# Option_DDR3_96ball.net
KiCad netlist of a schematic drawn in Altium Designer
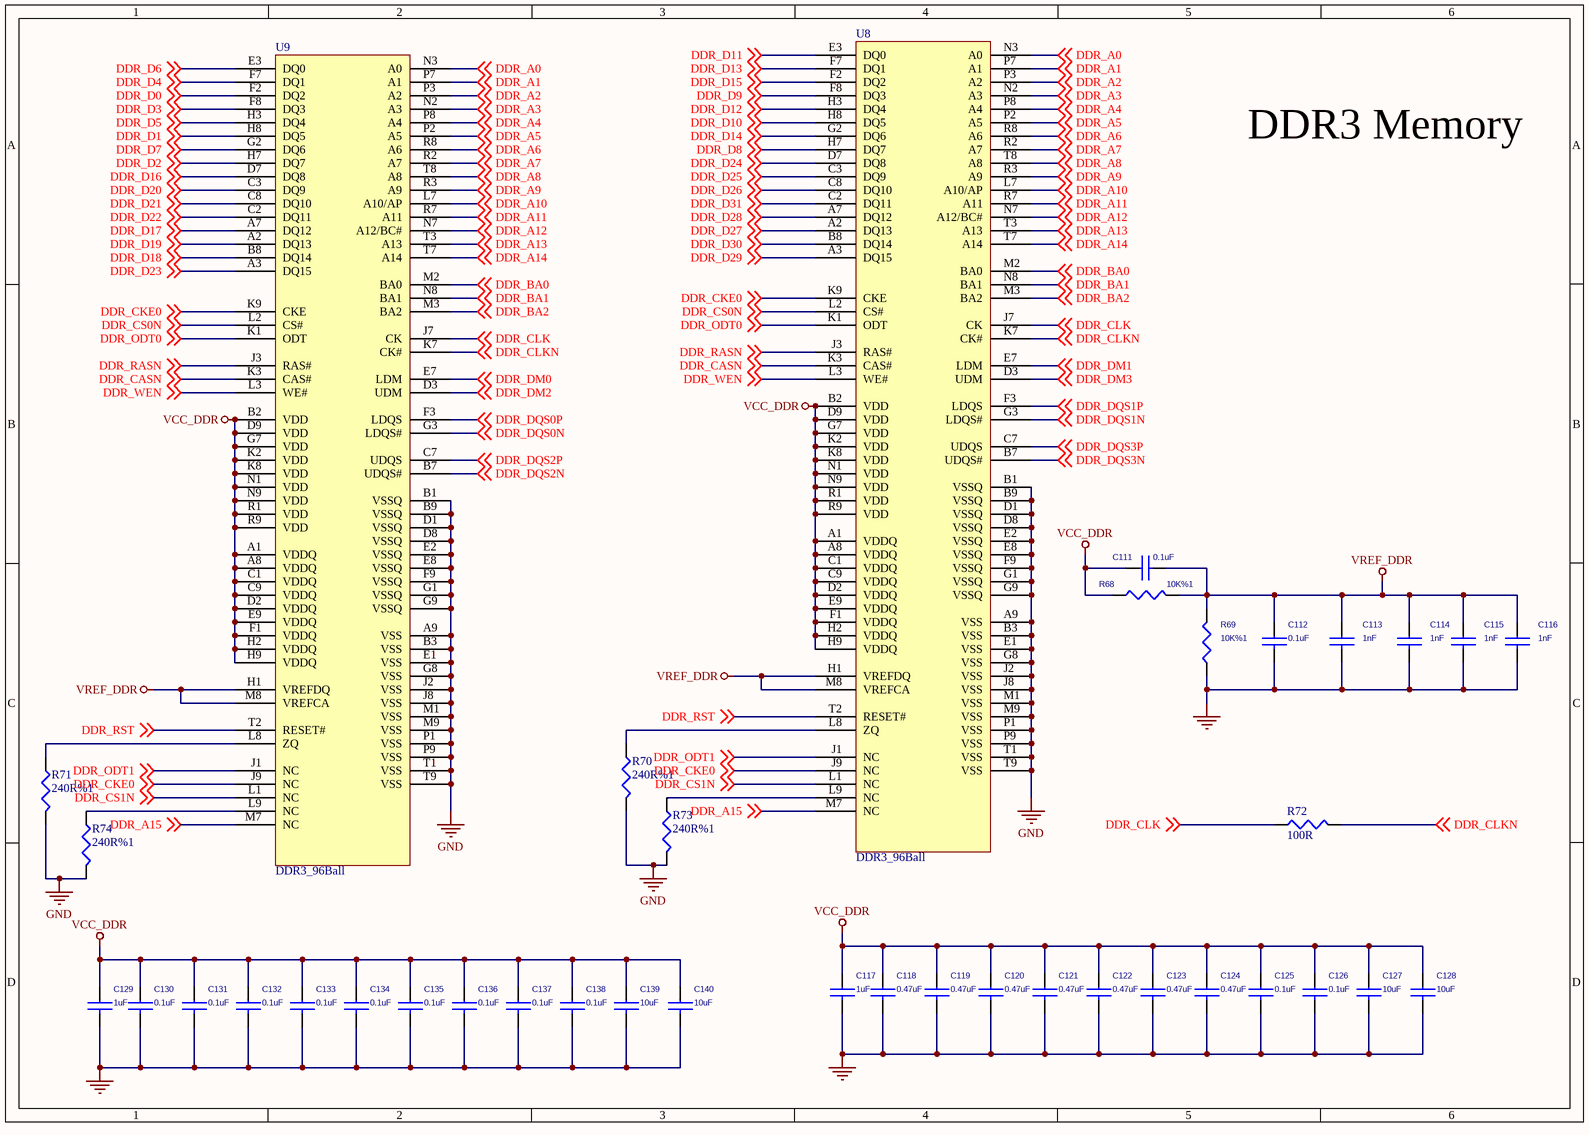
[diagram p0: Option_DDR3_96ball.SchDoc]

(export (version "E")
  (design (tool "Eeschema 10.0.6"))
  (components
    (comp (ref "C111") (value "0.1uF") (footprint "C0402") (libsource (lib "*") (part "CAP NP_0")))
    (comp (ref "C112") (value "0.1uF") (footprint "C0402") (libsource (lib "*") (part "CAP NP_0")))
    (comp (ref "C113") (value "1nF") (footprint "C0402") (libsource (lib "*") (part "CAP NP_0")))
    (comp (ref "C114") (value "1nF") (footprint "C0402") (libsource (lib "*") (part "CAP NP_0")))
    (comp (ref "C115") (value "1nF") (footprint "C0402") (libsource (lib "*") (part "CAP NP_0")))
    (comp (ref "C116") (value "1nF") (footprint "C0402") (libsource (lib "*") (part "CAP NP_0")))
    (comp (ref "C117")
      (value "1uF")
      (footprint "C0402")
      (description "RoHS CHIP CAP 1uF +10/-10% X5R")
      (libsource (lib "*") (part "CAP NP"))
    )
    (comp (ref "C118")
      (value "0.47uF")
      (footprint "C0402")
      (description "RoHS CHIP CAP 1uF +10/-10% X5R")
      (libsource (lib "*") (part "CAP NP"))
    )
    (comp (ref "C119")
      (value "0.47uF")
      (footprint "C0402")
      (description "RoHS CHIP CAP 1uF +10/-10% X5R")
      (libsource (lib "*") (part "CAP NP"))
    )
    (comp (ref "C120")
      (value "0.47uF")
      (footprint "C0402")
      (description "RoHS CHIP CAP 1uF +10/-10% X5R")
      (libsource (lib "*") (part "CAP NP"))
    )
    (comp (ref "C121")
      (value "0.47uF")
      (footprint "C0402")
      (description "RoHS CHIP CAP 1uF +10/-10% X5R")
      (libsource (lib "*") (part "CAP NP"))
    )
    (comp (ref "C122")
      (value "0.47uF")
      (footprint "C0402")
      (description "RoHS CHIP CAP 1uF +10/-10% X5R")
      (libsource (lib "*") (part "CAP NP"))
    )
    (comp (ref "C123")
      (value "0.47uF")
      (footprint "C0402")
      (description "RoHS CHIP CAP 1uF +10/-10% X5R")
      (libsource (lib "*") (part "CAP NP"))
    )
    (comp (ref "C124")
      (value "0.47uF")
      (footprint "C0402")
      (description "RoHS CHIP CAP 1uF +10/-10% X5R")
      (libsource (lib "*") (part "CAP NP"))
    )
    (comp (ref "C125")
      (value "0.1uF")
      (footprint "C0402")
      (description "RoHS CHIP CAP 0.1uF +10/-10% X7R")
      (libsource (lib "*") (part "CAP NP"))
    )
    (comp (ref "C126")
      (value "0.1uF")
      (footprint "C0402")
      (description "RoHS CHIP CAP 0.1uF +10/-10% X7R")
      (libsource (lib "*") (part "CAP NP"))
    )
    (comp (ref "C127")
      (value "10uF")
      (footprint "C0805")
      (description "RoHS CHIP CAP 0.1uF +10/-10% X7R")
      (libsource (lib "*") (part "CAP NP"))
    )
    (comp (ref "C128")
      (value "10uF")
      (footprint "C0805")
      (description "RoHS CHIP CAP 0.1uF +10/-10% X7R")
      (libsource (lib "*") (part "CAP NP"))
    )
    (comp (ref "C129")
      (value "1uF")
      (footprint "C0402")
      (description "RoHS CHIP CAP 1uF +10/-10% X5R")
      (libsource (lib "*") (part "CAP NP"))
    )
    (comp (ref "C130")
      (value "0.1uF")
      (footprint "C0402")
      (description "RoHS CHIP CAP 1uF +10/-10% X5R")
      (libsource (lib "*") (part "CAP NP"))
    )
    (comp (ref "C131")
      (value "0.1uF")
      (footprint "C0402")
      (description "RoHS CHIP CAP 0.1uF +10/-10% X7R")
      (libsource (lib "*") (part "CAP NP"))
    )
    (comp (ref "C132")
      (value "0.1uF")
      (footprint "C0402")
      (description "RoHS CHIP CAP 0.1uF +10/-10% X7R")
      (libsource (lib "*") (part "CAP NP"))
    )
    (comp (ref "C133")
      (value "0.1uF")
      (footprint "C0402")
      (description "RoHS CHIP CAP 0.1uF +10/-10% X7R")
      (libsource (lib "*") (part "CAP NP"))
    )
    (comp (ref "C134")
      (value "0.1uF")
      (footprint "C0402")
      (description "RoHS CHIP CAP 0.1uF +10/-10% X7R")
      (libsource (lib "*") (part "CAP NP"))
    )
    (comp (ref "C135")
      (value "0.1uF")
      (footprint "C0402")
      (description "RoHS CHIP CAP 0.1uF +10/-10% X7R")
      (libsource (lib "*") (part "CAP NP"))
    )
    (comp (ref "C136")
      (value "0.1uF")
      (footprint "C0402")
      (description "RoHS CHIP CAP 0.1uF +10/-10% X7R")
      (libsource (lib "*") (part "CAP NP"))
    )
    (comp (ref "C137")
      (value "0.1uF")
      (footprint "C0402")
      (description "RoHS CHIP CAP 0.1uF +10/-10% X7R")
      (libsource (lib "*") (part "CAP NP"))
    )
    (comp (ref "C138")
      (value "0.1uF")
      (footprint "C0402")
      (description "RoHS CHIP CAP 0.1uF +10/-10% X7R")
      (libsource (lib "*") (part "CAP NP"))
    )
    (comp (ref "C139")
      (value "10uF")
      (footprint "C0805")
      (description "RoHS CHIP CAP 0.1uF +10/-10% X7R")
      (libsource (lib "*") (part "CAP NP"))
    )
    (comp (ref "C140")
      (value "10uF")
      (footprint "C0805")
      (description "RoHS CHIP CAP 0.1uF +10/-10% X7R")
      (libsource (lib "*") (part "CAP NP"))
    )
    (comp (ref "R68")
      (value "10K%1")
      (footprint "R0402")
      (description "贴片电阻")
      (libsource (lib "*") (part "RESISTOR_0"))
    )
    (comp (ref "R69")
      (value "10K%1")
      (footprint "R0402")
      (description "贴片电阻")
      (libsource (lib "*") (part "RESISTOR_0"))
    )
    (comp (ref "R70")
      (value "240R%1")
      (footprint "R0402")
      (libsource (lib "RK3128_BETA_V03_20151231_Library") (part "RESISTOR"))
    )
    (comp (ref "R71")
      (value "240R%1")
      (footprint "R0402")
      (libsource (lib "RK3128_BETA_V03_20151231_Library") (part "RESISTOR"))
    )
    (comp (ref "R72")
      (value "100R")
      (footprint "R0402")
      (libsource (lib "RK3128_BETA_V03_20151231_Library") (part "RESISTOR"))
    )
    (comp (ref "R73")
      (value "240R%1")
      (footprint "R0402")
      (libsource (lib "RK3128_BETA_V03_20151231_Library") (part "RESISTOR"))
    )
    (comp (ref "R74")
      (value "240R%1")
      (footprint "R0402")
      (libsource (lib "RK3128_BETA_V03_20151231_Library") (part "RESISTOR"))
    )
    (comp (ref "U8") (value "DDR3_96Ball") (libsource (lib "*") (part "DDR3_96Ball")))
    (comp (ref "U9") (value "DDR3_96Ball") (libsource (lib "*") (part "DDR3_96Ball")))
  )
  (nets
    (net (code "1") (name "DDR_A0") (class "Default")
      (node (ref "U8") (pin "N3") (pinfunction "A0_N3") (pintype "passive"))
      (node (ref "U9") (pin "N3") (pinfunction "A0_N3") (pintype "passive"))
    )
    (net (code "2") (name "DDR_A1") (class "Default")
      (node (ref "U8") (pin "P7") (pinfunction "A1_P7") (pintype "passive"))
      (node (ref "U9") (pin "P7") (pinfunction "A1_P7") (pintype "passive"))
    )
    (net (code "3") (name "DDR_A2") (class "Default")
      (node (ref "U8") (pin "P3") (pinfunction "A2_P3") (pintype "passive"))
      (node (ref "U9") (pin "P3") (pinfunction "A2_P3") (pintype "passive"))
    )
    (net (code "4") (name "DDR_A3") (class "Default")
      (node (ref "U8") (pin "N2") (pinfunction "A3_N2") (pintype "passive"))
      (node (ref "U9") (pin "N2") (pinfunction "A3_N2") (pintype "passive"))
    )
    (net (code "5") (name "DDR_A4") (class "Default")
      (node (ref "U8") (pin "P8") (pinfunction "A4_P8") (pintype "passive"))
      (node (ref "U9") (pin "P8") (pinfunction "A4_P8") (pintype "passive"))
    )
    (net (code "6") (name "DDR_A5") (class "Default")
      (node (ref "U8") (pin "P2") (pinfunction "A5_P2") (pintype "passive"))
      (node (ref "U9") (pin "P2") (pinfunction "A5_P2") (pintype "passive"))
    )
    (net (code "7") (name "DDR_A6") (class "Default")
      (node (ref "U8") (pin "R8") (pinfunction "A6_R8") (pintype "passive"))
      (node (ref "U9") (pin "R8") (pinfunction "A6_R8") (pintype "passive"))
    )
    (net (code "8") (name "DDR_A7") (class "Default")
      (node (ref "U8") (pin "R2") (pinfunction "A7_R2") (pintype "passive"))
      (node (ref "U9") (pin "R2") (pinfunction "A7_R2") (pintype "passive"))
    )
    (net (code "9") (name "DDR_A8") (class "Default")
      (node (ref "U8") (pin "T8") (pinfunction "A8_T8") (pintype "passive"))
      (node (ref "U9") (pin "T8") (pinfunction "A8_T8") (pintype "passive"))
    )
    (net (code "10") (name "DDR_A9") (class "Default")
      (node (ref "U8") (pin "R3") (pinfunction "A9_R3") (pintype "passive"))
      (node (ref "U9") (pin "R3") (pinfunction "A9_R3") (pintype "passive"))
    )
    (net (code "11") (name "DDR_A10") (class "Default")
      (node (ref "U8") (pin "L7") (pinfunction "A10/AP_L7") (pintype "passive"))
      (node (ref "U9") (pin "L7") (pinfunction "A10/AP_L7") (pintype "passive"))
    )
    (net (code "12") (name "DDR_A11") (class "Default")
      (node (ref "U8") (pin "R7") (pinfunction "A11_R7") (pintype "passive"))
      (node (ref "U9") (pin "R7") (pinfunction "A11_R7") (pintype "passive"))
    )
    (net (code "13") (name "DDR_A12") (class "Default")
      (node (ref "U8") (pin "N7") (pinfunction "A12/BC#_N7") (pintype "passive"))
      (node (ref "U9") (pin "N7") (pinfunction "A12/BC#_N7") (pintype "passive"))
    )
    (net (code "14") (name "DDR_A13") (class "Default")
      (node (ref "U8") (pin "T3") (pinfunction "A13_T3") (pintype "passive"))
      (node (ref "U9") (pin "T3") (pinfunction "A13_T3") (pintype "passive"))
    )
    (net (code "15") (name "DDR_A14") (class "Default")
      (node (ref "U8") (pin "T7") (pinfunction "A14_T7") (pintype "passive"))
      (node (ref "U9") (pin "T7") (pinfunction "A14_T7") (pintype "passive"))
    )
    (net (code "16") (name "DDR_A15") (class "Default")
      (node (ref "U8") (pin "M7") (pinfunction "NC_M7") (pintype "passive"))
      (node (ref "U9") (pin "M7") (pinfunction "NC_M7") (pintype "passive"))
    )
    (net (code "17") (name "DDR_BA0") (class "Default")
      (node (ref "U8") (pin "M2") (pinfunction "BA0_M2") (pintype "passive"))
      (node (ref "U9") (pin "M2") (pinfunction "BA0_M2") (pintype "passive"))
    )
    (net (code "18") (name "DDR_BA1") (class "Default")
      (node (ref "U8") (pin "N8") (pinfunction "BA1_N8") (pintype "passive"))
      (node (ref "U9") (pin "N8") (pinfunction "BA1_N8") (pintype "passive"))
    )
    (net (code "19") (name "DDR_BA2") (class "Default")
      (node (ref "U8") (pin "M3") (pinfunction "BA2_M3") (pintype "passive"))
      (node (ref "U9") (pin "M3") (pinfunction "BA2_M3") (pintype "passive"))
    )
    (net (code "20") (name "DDR_CASN") (class "Default")
      (node (ref "U8") (pin "K3") (pinfunction "CAS#_K3") (pintype "passive"))
      (node (ref "U9") (pin "K3") (pinfunction "CAS#_K3") (pintype "passive"))
    )
    (net (code "21") (name "DDR_CKE0") (class "Default")
      (node (ref "U8") (pin "J9") (pinfunction "NC_J9") (pintype "passive"))
      (node (ref "U8") (pin "K9") (pinfunction "CKE_K9") (pintype "passive"))
      (node (ref "U9") (pin "J9") (pinfunction "NC_J9") (pintype "passive"))
      (node (ref "U9") (pin "K9") (pinfunction "CKE_K9") (pintype "passive"))
    )
    (net (code "22") (name "DDR_CLK") (class "Default")
      (node (ref "R72") (pin "1") (pinfunction "1_1") (pintype "passive"))
      (node (ref "U8") (pin "J7") (pinfunction "CK_J7") (pintype "passive"))
      (node (ref "U9") (pin "J7") (pinfunction "CK_J7") (pintype "passive"))
    )
    (net (code "23") (name "DDR_CLKN") (class "Default")
      (node (ref "R72") (pin "2") (pinfunction "2_2") (pintype "passive"))
      (node (ref "U8") (pin "K7") (pinfunction "CK#_K7") (pintype "passive"))
      (node (ref "U9") (pin "K7") (pinfunction "CK#_K7") (pintype "passive"))
    )
    (net (code "24") (name "DDR_CS0N") (class "Default")
      (node (ref "U8") (pin "L2") (pinfunction "CS#_L2") (pintype "passive"))
      (node (ref "U9") (pin "L2") (pinfunction "CS#_L2") (pintype "passive"))
    )
    (net (code "25") (name "DDR_CS1N") (class "Default")
      (node (ref "U8") (pin "L1") (pinfunction "NC_L1") (pintype "passive"))
      (node (ref "U9") (pin "L1") (pinfunction "NC_L1") (pintype "passive"))
    )
    (net (code "26") (name "DDR_D0") (class "Default")
      (node (ref "U9") (pin "F2") (pinfunction "DQ2_F2") (pintype "passive"))
    )
    (net (code "27") (name "DDR_D1") (class "Default")
      (node (ref "U9") (pin "H8") (pinfunction "DQ5_H8") (pintype "passive"))
    )
    (net (code "28") (name "DDR_D2") (class "Default")
      (node (ref "U9") (pin "H7") (pinfunction "DQ7_H7") (pintype "passive"))
    )
    (net (code "29") (name "DDR_D3") (class "Default")
      (node (ref "U9") (pin "F8") (pinfunction "DQ3_F8") (pintype "passive"))
    )
    (net (code "30") (name "DDR_D4") (class "Default")
      (node (ref "U9") (pin "F7") (pinfunction "DQ1_F7") (pintype "passive"))
    )
    (net (code "31") (name "DDR_D5") (class "Default")
      (node (ref "U9") (pin "H3") (pinfunction "DQ4_H3") (pintype "passive"))
    )
    (net (code "32") (name "DDR_D6") (class "Default")
      (node (ref "U9") (pin "E3") (pinfunction "DQ0_E3") (pintype "passive"))
    )
    (net (code "33") (name "DDR_D7") (class "Default")
      (node (ref "U9") (pin "G2") (pinfunction "DQ6_G2") (pintype "passive"))
    )
    (net (code "34") (name "DDR_D8") (class "Default")
      (node (ref "U8") (pin "H7") (pinfunction "DQ7_H7") (pintype "passive"))
    )
    (net (code "35") (name "DDR_D9") (class "Default")
      (node (ref "U8") (pin "F8") (pinfunction "DQ3_F8") (pintype "passive"))
    )
    (net (code "36") (name "DDR_D10") (class "Default")
      (node (ref "U8") (pin "H8") (pinfunction "DQ5_H8") (pintype "passive"))
    )
    (net (code "37") (name "DDR_D11") (class "Default")
      (node (ref "U8") (pin "E3") (pinfunction "DQ0_E3") (pintype "passive"))
    )
    (net (code "38") (name "DDR_D12") (class "Default")
      (node (ref "U8") (pin "H3") (pinfunction "DQ4_H3") (pintype "passive"))
    )
    (net (code "39") (name "DDR_D13") (class "Default")
      (node (ref "U8") (pin "F7") (pinfunction "DQ1_F7") (pintype "passive"))
    )
    (net (code "40") (name "DDR_D14") (class "Default")
      (node (ref "U8") (pin "G2") (pinfunction "DQ6_G2") (pintype "passive"))
    )
    (net (code "41") (name "DDR_D15") (class "Default")
      (node (ref "U8") (pin "F2") (pinfunction "DQ2_F2") (pintype "passive"))
    )
    (net (code "42") (name "DDR_D16") (class "Default")
      (node (ref "U9") (pin "D7") (pinfunction "DQ8_D7") (pintype "passive"))
    )
    (net (code "43") (name "DDR_D17") (class "Default")
      (node (ref "U9") (pin "A7") (pinfunction "DQ12_A7") (pintype "passive"))
    )
    (net (code "44") (name "DDR_D18") (class "Default")
      (node (ref "U9") (pin "B8") (pinfunction "DQ14_B8") (pintype "passive"))
    )
    (net (code "45") (name "DDR_D19") (class "Default")
      (node (ref "U9") (pin "A2") (pinfunction "DQ13_A2") (pintype "passive"))
    )
    (net (code "46") (name "DDR_D20") (class "Default")
      (node (ref "U9") (pin "C3") (pinfunction "DQ9_C3") (pintype "passive"))
    )
    (net (code "47") (name "DDR_D21") (class "Default")
      (node (ref "U9") (pin "C8") (pinfunction "DQ10_C8") (pintype "passive"))
    )
    (net (code "48") (name "DDR_D22") (class "Default")
      (node (ref "U9") (pin "C2") (pinfunction "DQ11_C2") (pintype "passive"))
    )
    (net (code "49") (name "DDR_D23") (class "Default")
      (node (ref "U9") (pin "A3") (pinfunction "DQ15_A3") (pintype "passive"))
    )
    (net (code "50") (name "DDR_D24") (class "Default")
      (node (ref "U8") (pin "D7") (pinfunction "DQ8_D7") (pintype "passive"))
    )
    (net (code "51") (name "DDR_D25") (class "Default")
      (node (ref "U8") (pin "C3") (pinfunction "DQ9_C3") (pintype "passive"))
    )
    (net (code "52") (name "DDR_D26") (class "Default")
      (node (ref "U8") (pin "C8") (pinfunction "DQ10_C8") (pintype "passive"))
    )
    (net (code "53") (name "DDR_D27") (class "Default")
      (node (ref "U8") (pin "A2") (pinfunction "DQ13_A2") (pintype "passive"))
    )
    (net (code "54") (name "DDR_D28") (class "Default")
      (node (ref "U8") (pin "A7") (pinfunction "DQ12_A7") (pintype "passive"))
    )
    (net (code "55") (name "DDR_D29") (class "Default")
      (node (ref "U8") (pin "A3") (pinfunction "DQ15_A3") (pintype "passive"))
    )
    (net (code "56") (name "DDR_D30") (class "Default")
      (node (ref "U8") (pin "B8") (pinfunction "DQ14_B8") (pintype "passive"))
    )
    (net (code "57") (name "DDR_D31") (class "Default")
      (node (ref "U8") (pin "C2") (pinfunction "DQ11_C2") (pintype "passive"))
    )
    (net (code "58") (name "DDR_DM0") (class "Default")
      (node (ref "U9") (pin "E7") (pinfunction "LDM_E7") (pintype "passive"))
    )
    (net (code "59") (name "DDR_DM1") (class "Default")
      (node (ref "U8") (pin "E7") (pinfunction "LDM_E7") (pintype "passive"))
    )
    (net (code "60") (name "DDR_DM2") (class "Default")
      (node (ref "U9") (pin "D3") (pinfunction "UDM_D3") (pintype "passive"))
    )
    (net (code "61") (name "DDR_DM3") (class "Default")
      (node (ref "U8") (pin "D3") (pinfunction "UDM_D3") (pintype "passive"))
    )
    (net (code "62") (name "DDR_DQS0N") (class "Default")
      (node (ref "U9") (pin "G3") (pinfunction "LDQS#_G3") (pintype "passive"))
    )
    (net (code "63") (name "DDR_DQS0P") (class "Default")
      (node (ref "U9") (pin "F3") (pinfunction "LDQS_F3") (pintype "passive"))
    )
    (net (code "64") (name "DDR_DQS1N") (class "Default")
      (node (ref "U8") (pin "G3") (pinfunction "LDQS#_G3") (pintype "passive"))
    )
    (net (code "65") (name "DDR_DQS1P") (class "Default")
      (node (ref "U8") (pin "F3") (pinfunction "LDQS_F3") (pintype "passive"))
    )
    (net (code "66") (name "DDR_DQS2N") (class "Default")
      (node (ref "U9") (pin "B7") (pinfunction "UDQS#_B7") (pintype "passive"))
    )
    (net (code "67") (name "DDR_DQS2P") (class "Default")
      (node (ref "U9") (pin "C7") (pinfunction "UDQS_C7") (pintype "passive"))
    )
    (net (code "68") (name "DDR_DQS3N") (class "Default")
      (node (ref "U8") (pin "B7") (pinfunction "UDQS#_B7") (pintype "passive"))
    )
    (net (code "69") (name "DDR_DQS3P") (class "Default")
      (node (ref "U8") (pin "C7") (pinfunction "UDQS_C7") (pintype "passive"))
    )
    (net (code "70") (name "DDR_ODT0") (class "Default")
      (node (ref "U8") (pin "K1") (pinfunction "ODT_K1") (pintype "passive"))
      (node (ref "U9") (pin "K1") (pinfunction "ODT_K1") (pintype "passive"))
    )
    (net (code "71") (name "DDR_ODT1") (class "Default")
      (node (ref "U8") (pin "J1") (pinfunction "NC_J1") (pintype "passive"))
      (node (ref "U9") (pin "J1") (pinfunction "NC_J1") (pintype "passive"))
    )
    (net (code "72") (name "DDR_RASN") (class "Default")
      (node (ref "U8") (pin "J3") (pinfunction "RAS#_J3") (pintype "passive"))
      (node (ref "U9") (pin "J3") (pinfunction "RAS#_J3") (pintype "passive"))
    )
    (net (code "73") (name "DDR_RST") (class "Default")
      (node (ref "U8") (pin "T2") (pinfunction "RESET#_T2") (pintype "passive"))
      (node (ref "U9") (pin "T2") (pinfunction "RESET#_T2") (pintype "passive"))
    )
    (net (code "74") (name "DDR_WEN") (class "Default")
      (node (ref "U8") (pin "L3") (pinfunction "WE#_L3") (pintype "passive"))
      (node (ref "U9") (pin "L3") (pinfunction "WE#_L3") (pintype "passive"))
    )
    (net (code "75") (name "GND") (class "Default")
      (node (ref "C112") (pin "2") (pinfunction "2_2") (pintype "passive"))
      (node (ref "C113") (pin "2") (pinfunction "2_2") (pintype "passive"))
      (node (ref "C114") (pin "2") (pinfunction "2_2") (pintype "passive"))
      (node (ref "C115") (pin "2") (pinfunction "2_2") (pintype "passive"))
      (node (ref "C116") (pin "2") (pinfunction "2_2") (pintype "passive"))
      (node (ref "C117") (pin "2") (pinfunction "2_2") (pintype "passive"))
      (node (ref "C118") (pin "2") (pinfunction "2_2") (pintype "passive"))
      (node (ref "C119") (pin "2") (pinfunction "2_2") (pintype "passive"))
      (node (ref "C120") (pin "2") (pinfunction "2_2") (pintype "passive"))
      (node (ref "C121") (pin "2") (pinfunction "2_2") (pintype "passive"))
      (node (ref "C122") (pin "2") (pinfunction "2_2") (pintype "passive"))
      (node (ref "C123") (pin "2") (pinfunction "2_2") (pintype "passive"))
      (node (ref "C124") (pin "2") (pinfunction "2_2") (pintype "passive"))
      (node (ref "C125") (pin "2") (pinfunction "2_2") (pintype "passive"))
      (node (ref "C126") (pin "2") (pinfunction "2_2") (pintype "passive"))
      (node (ref "C127") (pin "2") (pinfunction "2_2") (pintype "passive"))
      (node (ref "C128") (pin "2") (pinfunction "2_2") (pintype "passive"))
      (node (ref "C129") (pin "2") (pinfunction "2_2") (pintype "passive"))
      (node (ref "C130") (pin "2") (pinfunction "2_2") (pintype "passive"))
      (node (ref "C131") (pin "2") (pinfunction "2_2") (pintype "passive"))
      (node (ref "C132") (pin "2") (pinfunction "2_2") (pintype "passive"))
      (node (ref "C133") (pin "2") (pinfunction "2_2") (pintype "passive"))
      (node (ref "C134") (pin "2") (pinfunction "2_2") (pintype "passive"))
      (node (ref "C135") (pin "2") (pinfunction "2_2") (pintype "passive"))
      (node (ref "C136") (pin "2") (pinfunction "2_2") (pintype "passive"))
      (node (ref "C137") (pin "2") (pinfunction "2_2") (pintype "passive"))
      (node (ref "C138") (pin "2") (pinfunction "2_2") (pintype "passive"))
      (node (ref "C139") (pin "2") (pinfunction "2_2") (pintype "passive"))
      (node (ref "C140") (pin "2") (pinfunction "2_2") (pintype "passive"))
      (node (ref "R69") (pin "1") (pinfunction "1_1") (pintype "passive"))
      (node (ref "R70") (pin "2") (pinfunction "2_2") (pintype "passive"))
      (node (ref "R71") (pin "2") (pinfunction "2_2") (pintype "passive"))
      (node (ref "R73") (pin "2") (pinfunction "2_2") (pintype "passive"))
      (node (ref "R74") (pin "2") (pinfunction "2_2") (pintype "passive"))
      (node (ref "U8") (pin "A9") (pinfunction "VSS_A9") (pintype "passive"))
      (node (ref "U8") (pin "B1") (pinfunction "VSSQ_B1") (pintype "passive"))
      (node (ref "U8") (pin "B3") (pinfunction "VSS_B3") (pintype "passive"))
      (node (ref "U8") (pin "B9") (pinfunction "VSSQ_B9") (pintype "passive"))
      (node (ref "U8") (pin "D1") (pinfunction "VSSQ_D1") (pintype "passive"))
      (node (ref "U8") (pin "D8") (pinfunction "VSSQ_D8") (pintype "passive"))
      (node (ref "U8") (pin "E1") (pinfunction "VSS_E1") (pintype "passive"))
      (node (ref "U8") (pin "E2") (pinfunction "VSSQ_E2") (pintype "passive"))
      (node (ref "U8") (pin "E8") (pinfunction "VSSQ_E8") (pintype "passive"))
      (node (ref "U8") (pin "F9") (pinfunction "VSSQ_F9") (pintype "passive"))
      (node (ref "U8") (pin "G1") (pinfunction "VSSQ_G1") (pintype "passive"))
      (node (ref "U8") (pin "G8") (pinfunction "VSS_G8") (pintype "passive"))
      (node (ref "U8") (pin "G9") (pinfunction "VSSQ_G9") (pintype "passive"))
      (node (ref "U8") (pin "J2") (pinfunction "VSS_J2") (pintype "passive"))
      (node (ref "U8") (pin "J8") (pinfunction "VSS_J8") (pintype "passive"))
      (node (ref "U8") (pin "M1") (pinfunction "VSS_M1") (pintype "passive"))
      (node (ref "U8") (pin "M9") (pinfunction "VSS_M9") (pintype "passive"))
      (node (ref "U8") (pin "P1") (pinfunction "VSS_P1") (pintype "passive"))
      (node (ref "U8") (pin "P9") (pinfunction "VSS_P9") (pintype "passive"))
      (node (ref "U8") (pin "T1") (pinfunction "VSS_T1") (pintype "passive"))
      (node (ref "U8") (pin "T9") (pinfunction "VSS_T9") (pintype "passive"))
      (node (ref "U9") (pin "A9") (pinfunction "VSS_A9") (pintype "passive"))
      (node (ref "U9") (pin "B1") (pinfunction "VSSQ_B1") (pintype "passive"))
      (node (ref "U9") (pin "B3") (pinfunction "VSS_B3") (pintype "passive"))
      (node (ref "U9") (pin "B9") (pinfunction "VSSQ_B9") (pintype "passive"))
      (node (ref "U9") (pin "D1") (pinfunction "VSSQ_D1") (pintype "passive"))
      (node (ref "U9") (pin "D8") (pinfunction "VSSQ_D8") (pintype "passive"))
      (node (ref "U9") (pin "E1") (pinfunction "VSS_E1") (pintype "passive"))
      (node (ref "U9") (pin "E2") (pinfunction "VSSQ_E2") (pintype "passive"))
      (node (ref "U9") (pin "E8") (pinfunction "VSSQ_E8") (pintype "passive"))
      (node (ref "U9") (pin "F9") (pinfunction "VSSQ_F9") (pintype "passive"))
      (node (ref "U9") (pin "G1") (pinfunction "VSSQ_G1") (pintype "passive"))
      (node (ref "U9") (pin "G8") (pinfunction "VSS_G8") (pintype "passive"))
      (node (ref "U9") (pin "G9") (pinfunction "VSSQ_G9") (pintype "passive"))
      (node (ref "U9") (pin "J2") (pinfunction "VSS_J2") (pintype "passive"))
      (node (ref "U9") (pin "J8") (pinfunction "VSS_J8") (pintype "passive"))
      (node (ref "U9") (pin "M1") (pinfunction "VSS_M1") (pintype "passive"))
      (node (ref "U9") (pin "M9") (pinfunction "VSS_M9") (pintype "passive"))
      (node (ref "U9") (pin "P1") (pinfunction "VSS_P1") (pintype "passive"))
      (node (ref "U9") (pin "P9") (pinfunction "VSS_P9") (pintype "passive"))
      (node (ref "U9") (pin "T1") (pinfunction "VSS_T1") (pintype "passive"))
      (node (ref "U9") (pin "T9") (pinfunction "VSS_T9") (pintype "passive"))
    )
    (net (code "76") (name "Net-(R73-Pad1)") (class "Default")
      (node (ref "R73") (pin "1") (pinfunction "1_1") (pintype "passive"))
      (node (ref "U8") (pin "L9") (pinfunction "NC_L9") (pintype "passive"))
    )
    (net (code "77") (name "Net-(R74-Pad1)") (class "Default")
      (node (ref "R74") (pin "1") (pinfunction "1_1") (pintype "passive"))
      (node (ref "U9") (pin "L9") (pinfunction "NC_L9") (pintype "passive"))
    )
    (net (code "78") (name "Net-(U8-ZQ)") (class "Default")
      (node (ref "R70") (pin "1") (pinfunction "1_1") (pintype "passive"))
      (node (ref "U8") (pin "L8") (pinfunction "ZQ_L8") (pintype "passive"))
    )
    (net (code "79") (name "Net-(U9-ZQ)") (class "Default")
      (node (ref "R71") (pin "1") (pinfunction "1_1") (pintype "passive"))
      (node (ref "U9") (pin "L8") (pinfunction "ZQ_L8") (pintype "passive"))
    )
    (net (code "80") (name "VCC_DDR") (class "Default")
      (node (ref "C111") (pin "1") (pinfunction "1_1") (pintype "passive"))
      (node (ref "C117") (pin "1") (pinfunction "1_1") (pintype "passive"))
      (node (ref "C118") (pin "1") (pinfunction "1_1") (pintype "passive"))
      (node (ref "C119") (pin "1") (pinfunction "1_1") (pintype "passive"))
      (node (ref "C120") (pin "1") (pinfunction "1_1") (pintype "passive"))
      (node (ref "C121") (pin "1") (pinfunction "1_1") (pintype "passive"))
      (node (ref "C122") (pin "1") (pinfunction "1_1") (pintype "passive"))
      (node (ref "C123") (pin "1") (pinfunction "1_1") (pintype "passive"))
      (node (ref "C124") (pin "1") (pinfunction "1_1") (pintype "passive"))
      (node (ref "C125") (pin "1") (pinfunction "1_1") (pintype "passive"))
      (node (ref "C126") (pin "1") (pinfunction "1_1") (pintype "passive"))
      (node (ref "C127") (pin "1") (pinfunction "1_1") (pintype "passive"))
      (node (ref "C128") (pin "1") (pinfunction "1_1") (pintype "passive"))
      (node (ref "C129") (pin "1") (pinfunction "1_1") (pintype "passive"))
      (node (ref "C130") (pin "1") (pinfunction "1_1") (pintype "passive"))
      (node (ref "C131") (pin "1") (pinfunction "1_1") (pintype "passive"))
      (node (ref "C132") (pin "1") (pinfunction "1_1") (pintype "passive"))
      (node (ref "C133") (pin "1") (pinfunction "1_1") (pintype "passive"))
      (node (ref "C134") (pin "1") (pinfunction "1_1") (pintype "passive"))
      (node (ref "C135") (pin "1") (pinfunction "1_1") (pintype "passive"))
      (node (ref "C136") (pin "1") (pinfunction "1_1") (pintype "passive"))
      (node (ref "C137") (pin "1") (pinfunction "1_1") (pintype "passive"))
      (node (ref "C138") (pin "1") (pinfunction "1_1") (pintype "passive"))
      (node (ref "C139") (pin "1") (pinfunction "1_1") (pintype "passive"))
      (node (ref "C140") (pin "1") (pinfunction "1_1") (pintype "passive"))
      (node (ref "R68") (pin "1") (pinfunction "1_1") (pintype "passive"))
      (node (ref "U8") (pin "A1") (pinfunction "VDDQ_A1") (pintype "passive"))
      (node (ref "U8") (pin "A8") (pinfunction "VDDQ_A8") (pintype "passive"))
      (node (ref "U8") (pin "B2") (pinfunction "VDD_B2") (pintype "passive"))
      (node (ref "U8") (pin "C1") (pinfunction "VDDQ_C1") (pintype "passive"))
      (node (ref "U8") (pin "C9") (pinfunction "VDDQ_C9") (pintype "passive"))
      (node (ref "U8") (pin "D2") (pinfunction "VDDQ_D2") (pintype "passive"))
      (node (ref "U8") (pin "D9") (pinfunction "VDD_D9") (pintype "passive"))
      (node (ref "U8") (pin "E9") (pinfunction "VDDQ_E9") (pintype "passive"))
      (node (ref "U8") (pin "F1") (pinfunction "VDDQ_F1") (pintype "passive"))
      (node (ref "U8") (pin "G7") (pinfunction "VDD_G7") (pintype "passive"))
      (node (ref "U8") (pin "H2") (pinfunction "VDDQ_H2") (pintype "passive"))
      (node (ref "U8") (pin "H9") (pinfunction "VDDQ_H9") (pintype "passive"))
      (node (ref "U8") (pin "K2") (pinfunction "VDD_K2") (pintype "passive"))
      (node (ref "U8") (pin "K8") (pinfunction "VDD_K8") (pintype "passive"))
      (node (ref "U8") (pin "N1") (pinfunction "VDD_N1") (pintype "passive"))
      (node (ref "U8") (pin "N9") (pinfunction "VDD_N9") (pintype "passive"))
      (node (ref "U8") (pin "R1") (pinfunction "VDD_R1") (pintype "passive"))
      (node (ref "U8") (pin "R9") (pinfunction "VDD_R9") (pintype "passive"))
      (node (ref "U9") (pin "A1") (pinfunction "VDDQ_A1") (pintype "passive"))
      (node (ref "U9") (pin "A8") (pinfunction "VDDQ_A8") (pintype "passive"))
      (node (ref "U9") (pin "B2") (pinfunction "VDD_B2") (pintype "passive"))
      (node (ref "U9") (pin "C1") (pinfunction "VDDQ_C1") (pintype "passive"))
      (node (ref "U9") (pin "C9") (pinfunction "VDDQ_C9") (pintype "passive"))
      (node (ref "U9") (pin "D2") (pinfunction "VDDQ_D2") (pintype "passive"))
      (node (ref "U9") (pin "D9") (pinfunction "VDD_D9") (pintype "passive"))
      (node (ref "U9") (pin "E9") (pinfunction "VDDQ_E9") (pintype "passive"))
      (node (ref "U9") (pin "F1") (pinfunction "VDDQ_F1") (pintype "passive"))
      (node (ref "U9") (pin "G7") (pinfunction "VDD_G7") (pintype "passive"))
      (node (ref "U9") (pin "H2") (pinfunction "VDDQ_H2") (pintype "passive"))
      (node (ref "U9") (pin "H9") (pinfunction "VDDQ_H9") (pintype "passive"))
      (node (ref "U9") (pin "K2") (pinfunction "VDD_K2") (pintype "passive"))
      (node (ref "U9") (pin "K8") (pinfunction "VDD_K8") (pintype "passive"))
      (node (ref "U9") (pin "N1") (pinfunction "VDD_N1") (pintype "passive"))
      (node (ref "U9") (pin "N9") (pinfunction "VDD_N9") (pintype "passive"))
      (node (ref "U9") (pin "R1") (pinfunction "VDD_R1") (pintype "passive"))
      (node (ref "U9") (pin "R9") (pinfunction "VDD_R9") (pintype "passive"))
    )
    (net (code "81") (name "VREF_DDR") (class "Default")
      (node (ref "C111") (pin "2") (pinfunction "2_2") (pintype "passive"))
      (node (ref "C112") (pin "1") (pinfunction "1_1") (pintype "passive"))
      (node (ref "C113") (pin "1") (pinfunction "1_1") (pintype "passive"))
      (node (ref "C114") (pin "1") (pinfunction "1_1") (pintype "passive"))
      (node (ref "C115") (pin "1") (pinfunction "1_1") (pintype "passive"))
      (node (ref "C116") (pin "1") (pinfunction "1_1") (pintype "passive"))
      (node (ref "R68") (pin "2") (pinfunction "2_2") (pintype "passive"))
      (node (ref "R69") (pin "2") (pinfunction "2_2") (pintype "passive"))
      (node (ref "U8") (pin "H1") (pinfunction "VREFDQ_H1") (pintype "passive"))
      (node (ref "U8") (pin "M8") (pinfunction "VREFCA_M8") (pintype "passive"))
      (node (ref "U9") (pin "H1") (pinfunction "VREFDQ_H1") (pintype "passive"))
      (node (ref "U9") (pin "M8") (pinfunction "VREFCA_M8") (pintype "passive"))
    )
  )
)
